# Principal.net
KiCad netlist of a schematic drawn in Altium Designer
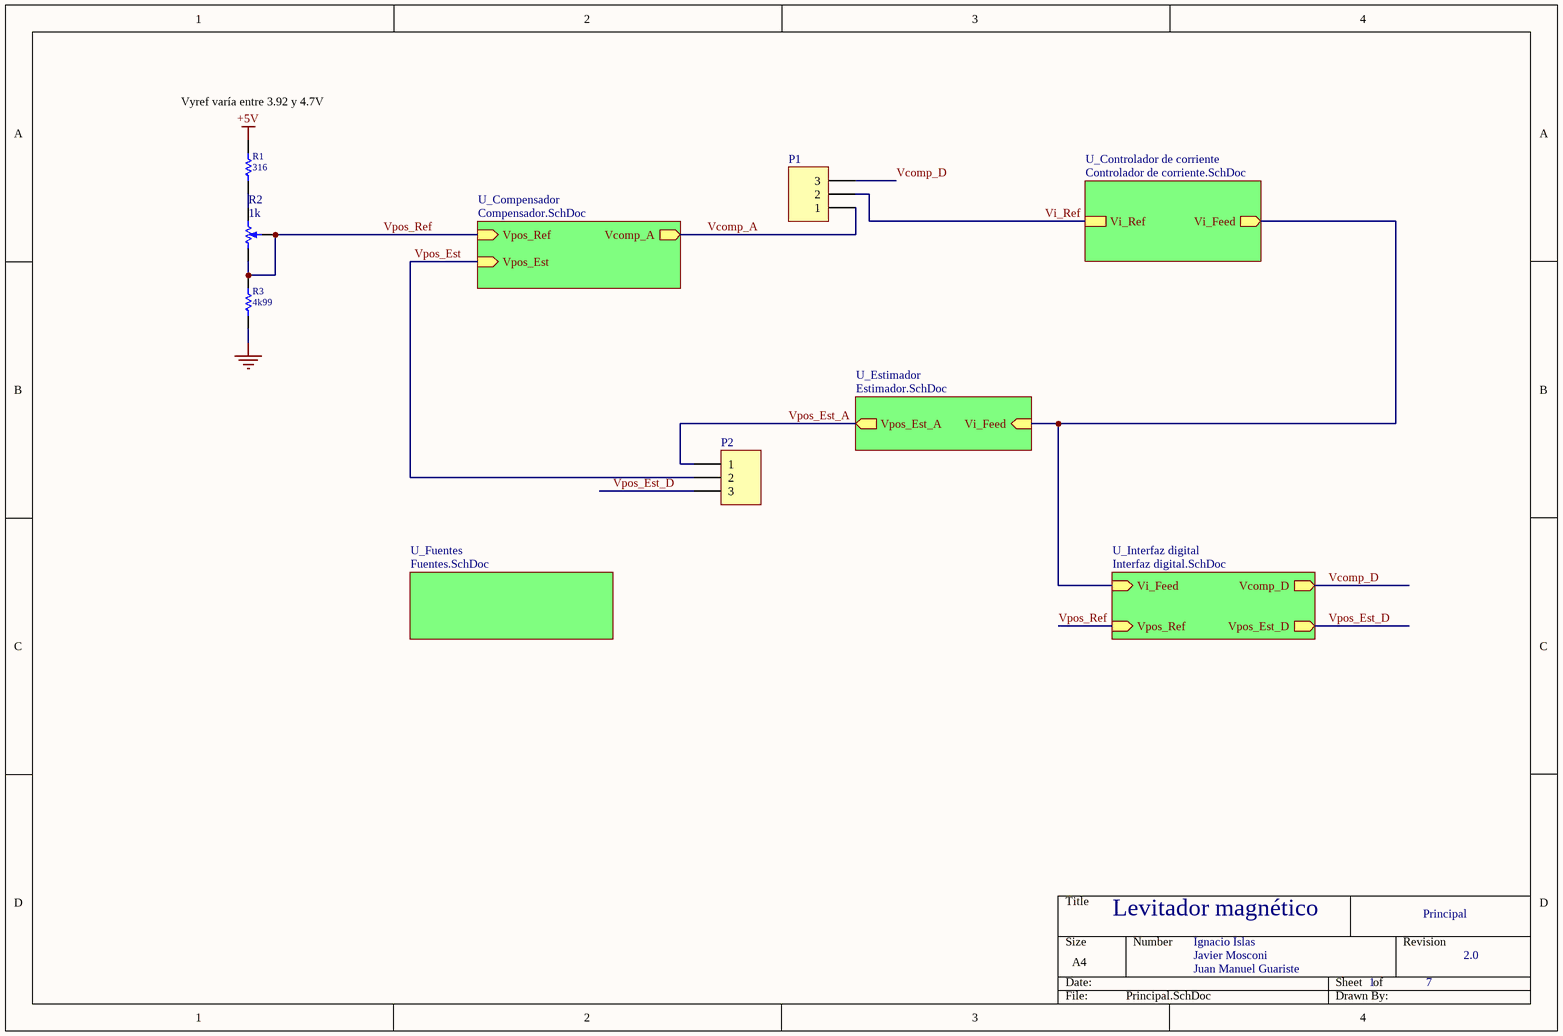
[diagram p0: Principal.SchDoc]

(export (version "E")
  (design (tool "Eeschema 10.0.6"))
  (components
    (comp (ref "P1")
      (value "Header 3")
      (footprint "HDR1X3")
      (description "TERM BLK 3P SIDE ENT 2.54MM PCB")
      (fields (field (name "MANUFACTURER") "TE Connectivity AMP Connectors"))
      (libsource (lib "Levitador_GMI") (part "Header 3"))
    )
    (comp (ref "P2")
      (value "Header 3")
      (footprint "HDR1X3")
      (description "TERM BLK 3P SIDE ENT 2.54MM PCB")
      (fields (field (name "MANUFACTURER") "TE Connectivity AMP Connectors"))
      (libsource (lib "") (part "Header 3_1"))
    )
    (comp (ref "R1")
      (value "316")
      (footprint "Levitador_GMI:R1206")
      (description "RES 316 OHM 1% 1/4W 1206")
      (fields (field (name "MANUFACTURER") "Stackpole Electronics Inc") (field (name "TOLERANCE") "1%"))
      (libsource (lib "Levitador_GMI") (part "R1206"))
    )
    (comp (ref "R2")
      (value "1k")
      (footprint "pote_5_pines_vertical")
      (description "POT 1K OHM 0.08W CARBON LINEAR")
      (fields (field (name "MANUFACTURER") "Bourns Inc.") (field (name "Comment") "Potenciometro"))
      (libsource (lib "Levitador_GMI") (part "Potenciometro"))
    )
    (comp (ref "R3")
      (value "4k99")
      (footprint "Levitador_GMI:R1206")
      (description "RES 4.99K OHM 1% 1/4W 1206")
      (fields (field (name "MANUFACTURER") "Stackpole Electronics Inc") (field (name "TOLERANCE") "1%"))
      (libsource (lib "Levitador_GMI") (part "R1206"))
    )
  )
  (nets
    (net (code "1") (name "+5V") (class "Default")
      (node (ref "R1") (pin "2") (pinfunction "2_2") (pintype "passive"))
    )
    (net (code "2") (name "/Vcomp_A") (class "Default")
      (node (ref "P1") (pin "1") (pinfunction "1_1") (pintype "passive"))
    )
    (net (code "3") (name "/Vcomp_D") (class "Default")
      (node (ref "P1") (pin "3") (pinfunction "3_3") (pintype "passive"))
    )
    (net (code "5") (name "/Vi_Ref") (class "Default")
      (node (ref "P1") (pin "2") (pinfunction "2_2") (pintype "passive"))
    )
    (net (code "6") (name "/Vpos_Est") (class "Default")
      (node (ref "P2") (pin "2") (pinfunction "2_2") (pintype "passive"))
    )
    (net (code "7") (name "/Vpos_Est_A") (class "Default")
      (node (ref "P2") (pin "1") (pinfunction "1_1") (pintype "passive"))
    )
    (net (code "8") (name "/Vpos_Est_D") (class "Default")
      (node (ref "P2") (pin "3") (pinfunction "3_3") (pintype "passive"))
    )
    (net (code "9") (name "/Vpos_Ref") (class "Default")
      (node (ref "R2") (pin "2") (pinfunction "W_2") (pintype "passive"))
      (node (ref "R2") (pin "3") (pinfunction "-_3") (pintype "passive"))
      (node (ref "R3") (pin "2") (pinfunction "2_2") (pintype "passive"))
    )
    (net (code "10") (name "GND") (class "Default")
      (node (ref "R3") (pin "1") (pinfunction "1_1") (pintype "passive"))
    )
    (net (code "11") (name "Net-(R2-+)") (class "Default")
      (node (ref "R1") (pin "1") (pinfunction "1_1") (pintype "passive"))
      (node (ref "R2") (pin "1") (pinfunction "+_1") (pintype "passive"))
    )
  )
)
